# lipo_board.net
KiCad netlist of a schematic drawn in Altium Designer
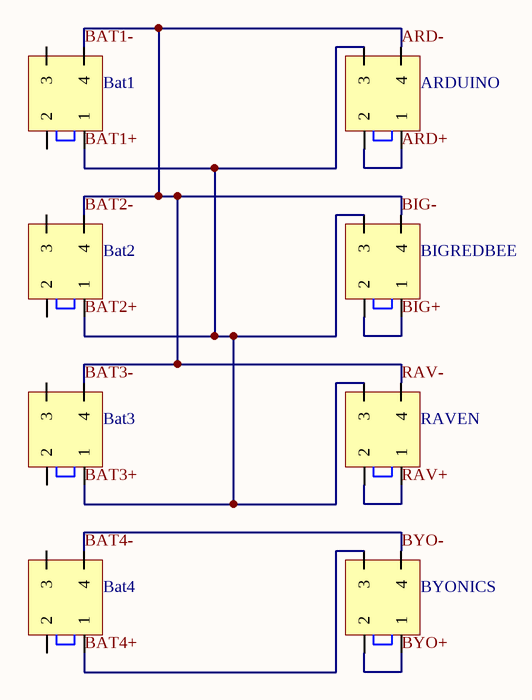
[diagram p0: lipo_board.SchDoc]

(export (version "E")
  (design (tool "Eeschema 10.0.6"))
  (components
    (comp (ref "ARDUINO")
      (value "5566-4")
      (footprint "Molex:5566-4")
      (libsource (lib "Molex") (part "5566-4"))
    )
    (comp (ref "Bat1") (value "5566-4") (footprint "Molex:5566-4") (libsource (lib "Molex") (part "5566-4")))
    (comp (ref "Bat2") (value "5566-4") (footprint "Molex:5566-4") (libsource (lib "Molex") (part "5566-4")))
    (comp (ref "Bat3") (value "5566-4") (footprint "Molex:5566-4") (libsource (lib "Molex") (part "5566-4")))
    (comp (ref "Bat4") (value "5566-4") (footprint "Molex:5566-4") (libsource (lib "Molex") (part "5566-4")))
    (comp (ref "BIGREDBEE")
      (value "5566-4")
      (footprint "Molex:5566-4")
      (libsource (lib "Molex") (part "5566-4"))
    )
    (comp (ref "BYONICS")
      (value "5566-4")
      (footprint "Molex:5566-4")
      (libsource (lib "Molex") (part "5566-4"))
    )
    (comp (ref "RAVEN") (value "5566-4") (footprint "Molex:5566-4") (libsource (lib "Molex") (part "5566-4")))
  )
  (nets
    (net (code "1") (name "/ARD+") (class "Default")
      (node (ref "ARDUINO") (pin "1") (pinfunction "1_1") (pintype "passive"))
      (node (ref "ARDUINO") (pin "2") (pinfunction "2_2") (pintype "passive"))
    )
    (net (code "2") (name "/ARD-") (class "Default")
      (node (ref "ARDUINO") (pin "4") (pinfunction "4_4") (pintype "passive"))
      (node (ref "BIGREDBEE") (pin "4") (pinfunction "4_4") (pintype "passive"))
      (node (ref "Bat1") (pin "4") (pinfunction "4_4") (pintype "passive"))
      (node (ref "Bat2") (pin "4") (pinfunction "4_4") (pintype "passive"))
      (node (ref "Bat3") (pin "4") (pinfunction "4_4") (pintype "passive"))
      (node (ref "RAVEN") (pin "4") (pinfunction "4_4") (pintype "passive"))
    )
    (net (code "3") (name "/BAT1+") (class "Default")
      (node (ref "ARDUINO") (pin "3") (pinfunction "3_3") (pintype "passive"))
      (node (ref "BIGREDBEE") (pin "3") (pinfunction "3_3") (pintype "passive"))
      (node (ref "Bat1") (pin "1") (pinfunction "1_1") (pintype "passive"))
      (node (ref "Bat2") (pin "1") (pinfunction "1_1") (pintype "passive"))
      (node (ref "Bat3") (pin "1") (pinfunction "1_1") (pintype "passive"))
      (node (ref "RAVEN") (pin "3") (pinfunction "3_3") (pintype "passive"))
    )
    (net (code "4") (name "/BAT4+") (class "Default")
      (node (ref "BYONICS") (pin "3") (pinfunction "3_3") (pintype "passive"))
      (node (ref "Bat4") (pin "1") (pinfunction "1_1") (pintype "passive"))
    )
    (net (code "5") (name "/BAT4-") (class "Default")
      (node (ref "BYONICS") (pin "4") (pinfunction "4_4") (pintype "passive"))
      (node (ref "Bat4") (pin "4") (pinfunction "4_4") (pintype "passive"))
    )
    (net (code "6") (name "/BIG+") (class "Default")
      (node (ref "BIGREDBEE") (pin "1") (pinfunction "1_1") (pintype "passive"))
      (node (ref "BIGREDBEE") (pin "2") (pinfunction "2_2") (pintype "passive"))
    )
    (net (code "7") (name "/BYO+") (class "Default")
      (node (ref "BYONICS") (pin "1") (pinfunction "1_1") (pintype "passive"))
      (node (ref "BYONICS") (pin "2") (pinfunction "2_2") (pintype "passive"))
    )
    (net (code "8") (name "/RAV+") (class "Default")
      (node (ref "RAVEN") (pin "1") (pinfunction "1_1") (pintype "passive"))
      (node (ref "RAVEN") (pin "2") (pinfunction "2_2") (pintype "passive"))
    )
    (net (code "9") (name "unconnected-(Bat1-Pad2)") (class "Default")
      (node (ref "Bat1") (pin "2") (pinfunction "2_2") (pintype "passive"))
    )
    (net (code "10") (name "unconnected-(Bat1-Pad3)") (class "Default")
      (node (ref "Bat1") (pin "3") (pinfunction "3_3") (pintype "passive"))
    )
    (net (code "11") (name "unconnected-(Bat2-Pad2)") (class "Default")
      (node (ref "Bat2") (pin "2") (pinfunction "2_2") (pintype "passive"))
    )
    (net (code "12") (name "unconnected-(Bat2-Pad3)") (class "Default")
      (node (ref "Bat2") (pin "3") (pinfunction "3_3") (pintype "passive"))
    )
    (net (code "13") (name "unconnected-(Bat3-Pad2)") (class "Default")
      (node (ref "Bat3") (pin "2") (pinfunction "2_2") (pintype "passive"))
    )
    (net (code "14") (name "unconnected-(Bat3-Pad3)") (class "Default")
      (node (ref "Bat3") (pin "3") (pinfunction "3_3") (pintype "passive"))
    )
    (net (code "15") (name "unconnected-(Bat4-Pad2)") (class "Default")
      (node (ref "Bat4") (pin "2") (pinfunction "2_2") (pintype "passive"))
    )
    (net (code "16") (name "unconnected-(Bat4-Pad3)") (class "Default")
      (node (ref "Bat4") (pin "3") (pinfunction "3_3") (pintype "passive"))
    )
  )
)
